# CAN.net
KiCad netlist of a schematic drawn in Altium Designer
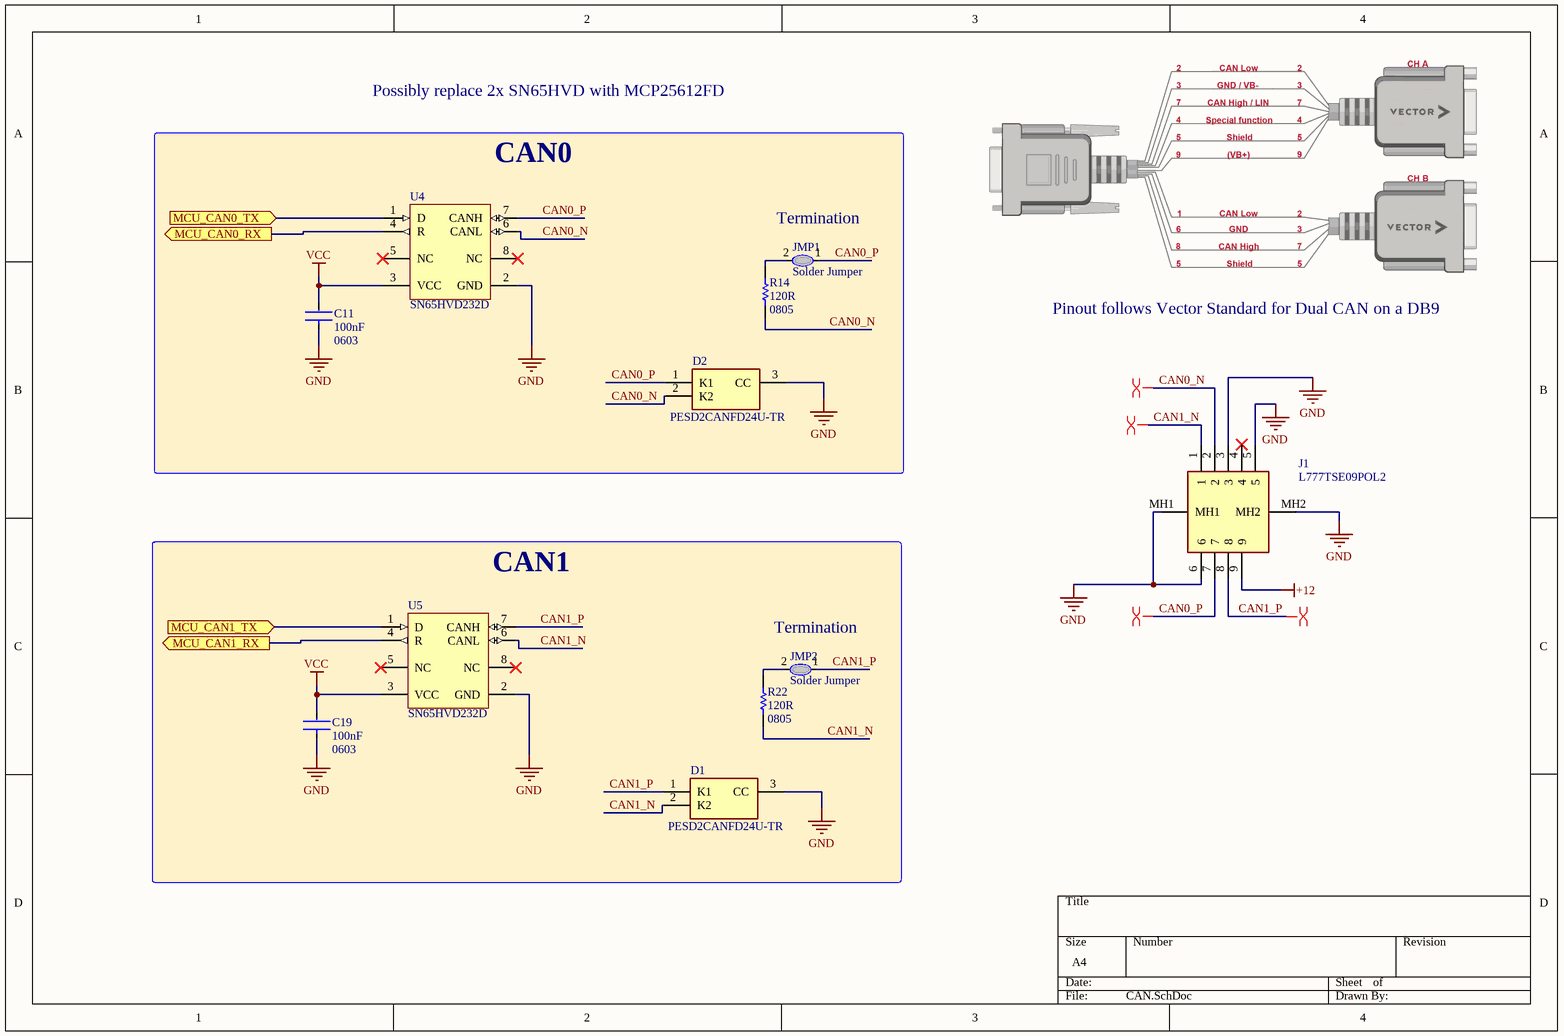
[diagram p0: CAN.SchDoc]

(export (version "E")
  (design (tool "Eeschema 10.0.6"))
  (components
    (comp (ref "C11")
      (value "CL10B104KB8WPNC")
      (footprint "FP-CL10-IPC_A")
      (description "Cap Ceramic 100nF 50V X7R ±10% Pad SMD 0603 +125°C T/R")
      (fields
        (field (name "CAPACITANCE") "100nF")
        (field (name "CASE/PACKAGE") "0603")
        (field (name "TOLERANCE") "10%")
      )
      (libsource (lib "Altium Content Vault") (part "b4654b650e69147ec39a6b967a45e02"))
    )
    (comp (ref "C19")
      (value "CL10B104KB8WPNC")
      (footprint "FP-CL10-IPC_A")
      (description "Cap Ceramic 100nF 50V X7R ±10% Pad SMD 0603 +125°C T/R")
      (fields
        (field (name "CAPACITANCE") "100nF")
        (field (name "CASE/PACKAGE") "0603")
        (field (name "TOLERANCE") "10%")
      )
      (libsource (lib "Altium Content Vault") (part "b4654b650e69147ec39a6b967a45e02"))
    )
    (comp (ref "D1")
      (value "PESD2CANFD24U-TR")
      (footprint "SOT95P230X110-3N")
      (description "Diode")
      (fields (field (name "MOUSER PART NUMBER") "771-PESD2CANFD24U-TR"))
      (libsource (lib "WiCAN_lib") (part "PESD2CANFD24U-TR"))
    )
    (comp (ref "D2")
      (value "PESD2CANFD24U-TR")
      (footprint "SOT95P230X110-3N")
      (description "Diode")
      (fields (field (name "MOUSER PART NUMBER") "771-PESD2CANFD24U-TR"))
      (libsource (lib "WiCAN_lib") (part "PESD2CANFD24U-TR"))
    )
    (comp (ref "J1")
      (value "L777TSE09POL2")
      (footprint "L777TSE09POL2")
      (description "Connector")
      (fields (field (name "MOUSER PART NUMBER") "523-L777TSE09POL2"))
      (libsource (lib "WiCAN_lib") (part "L777TSE09POL2"))
    )
    (comp (ref "JMP1")
      (value "Solder Jumper")
      (footprint "Solder Jumper")
      (libsource (lib "WiCAN_lib") (part "Solder Jumper"))
    )
    (comp (ref "JMP2")
      (value "Solder Jumper")
      (footprint "Solder Jumper")
      (libsource (lib "WiCAN_lib") (part "Solder Jumper"))
    )
    (comp (ref "R14")
      (value "ERJ-P06J121V")
      (footprint "RESC2013X70X40LL20T20")
      (fields
        (field (name "MANUFACTURER") "Panasonic")
        (field (name "RESISTANCE") "120R")
        (field (name "PACKAGE") "0805")
      )
      (libsource (lib "Altium Content Vault") (part "RES"))
    )
    (comp (ref "R22")
      (value "ERJ-P06J121V")
      (footprint "RESC2013X70X40LL20T20")
      (fields
        (field (name "MANUFACTURER") "Panasonic")
        (field (name "RESISTANCE") "120R")
        (field (name "PACKAGE") "0805")
      )
      (libsource (lib "Altium Content Vault") (part "RES"))
    )
    (comp (ref "U4")
      (value "SN65HVD232D")
      (footprint "D0008A_L")
      (description "3.3 V CAN Transceiver, 17 mA, -40 to 85 degC, 8-pin SOIC (D), Green (RoHS & no Sb/Br)")
      (fields (field (name "MANUFACTURER") "Texas Instruments"))
      (libsource (lib "Altium Content Vault") (part "TI-SN65HVD232-SOIC_D-8"))
    )
    (comp (ref "U5")
      (value "SN65HVD232D")
      (footprint "D0008A_L")
      (description "3.3 V CAN Transceiver, 17 mA, -40 to 85 degC, 8-pin SOIC (D), Green (RoHS & no Sb/Br)")
      (fields (field (name "MANUFACTURER") "Texas Instruments"))
      (libsource (lib "Altium Content Vault") (part "TI-SN65HVD232-SOIC_D-8"))
    )
  )
  (nets
    (net (code "1") (name "+12") (class "Default")
      (node (ref "J1") (pin "9") (pinfunction "9_9") (pintype "passive"))
    )
    (net (code "2") (name "/CAN0_N") (class "Default")
      (node (ref "D2") (pin "2") (pinfunction "K2_2") (pintype "passive"))
      (node (ref "J1") (pin "2") (pinfunction "2_2") (pintype "passive"))
      (node (ref "R14") (pin "2") (pinfunction "2_2") (pintype "passive"))
      (node (ref "U4") (pin "6") (pinfunction "CANL_6") (pintype "bidirectional"))
    )
    (net (code "3") (name "/CAN0_P") (class "Default")
      (node (ref "D2") (pin "1") (pinfunction "K1_1") (pintype "passive"))
      (node (ref "J1") (pin "7") (pinfunction "7_7") (pintype "passive"))
      (node (ref "JMP1") (pin "1") (pinfunction "1_1") (pintype "passive"))
      (node (ref "U4") (pin "7") (pinfunction "CANH_7") (pintype "bidirectional"))
    )
    (net (code "4") (name "/CAN1_N") (class "Default")
      (node (ref "D1") (pin "2") (pinfunction "K2_2") (pintype "passive"))
      (node (ref "J1") (pin "1") (pinfunction "1_1") (pintype "passive"))
      (node (ref "R22") (pin "2") (pinfunction "2_2") (pintype "passive"))
      (node (ref "U5") (pin "6") (pinfunction "CANL_6") (pintype "bidirectional"))
    )
    (net (code "5") (name "/CAN1_P") (class "Default")
      (node (ref "D1") (pin "1") (pinfunction "K1_1") (pintype "passive"))
      (node (ref "J1") (pin "8") (pinfunction "8_8") (pintype "passive"))
      (node (ref "JMP2") (pin "1") (pinfunction "1_1") (pintype "passive"))
      (node (ref "U5") (pin "7") (pinfunction "CANH_7") (pintype "bidirectional"))
    )
    (net (code "6") (name "/MCU_CAN0_RX") (class "Default")
      (node (ref "U4") (pin "4") (pinfunction "R_4") (pintype "output"))
    )
    (net (code "7") (name "/MCU_CAN0_TX") (class "Default")
      (node (ref "U4") (pin "1") (pinfunction "D_1") (pintype "input"))
    )
    (net (code "8") (name "/MCU_CAN1_RX") (class "Default")
      (node (ref "U5") (pin "4") (pinfunction "R_4") (pintype "output"))
    )
    (net (code "9") (name "/MCU_CAN1_TX") (class "Default")
      (node (ref "U5") (pin "1") (pinfunction "D_1") (pintype "input"))
    )
    (net (code "10") (name "GND") (class "Default")
      (node (ref "C11") (pin "1") (pinfunction "1_1") (pintype "passive"))
      (node (ref "C19") (pin "1") (pinfunction "1_1") (pintype "passive"))
      (node (ref "D1") (pin "3") (pinfunction "CC_3") (pintype "passive"))
      (node (ref "D2") (pin "3") (pinfunction "CC_3") (pintype "passive"))
      (node (ref "J1") (pin "3") (pinfunction "3_3") (pintype "passive"))
      (node (ref "J1") (pin "5") (pinfunction "5_5") (pintype "passive"))
      (node (ref "J1") (pin "6") (pinfunction "6_6") (pintype "passive"))
      (node (ref "J1") (pin "MH1") (pinfunction "MH1_MH1") (pintype "passive"))
      (node (ref "J1") (pin "MH2") (pinfunction "MH2_MH2") (pintype "passive"))
      (node (ref "U4") (pin "2") (pinfunction "GND_2") (pintype "power_in"))
      (node (ref "U5") (pin "2") (pinfunction "GND_2") (pintype "power_in"))
    )
    (net (code "11") (name "Net-(JMP1-Pad2)") (class "Default")
      (node (ref "JMP1") (pin "2") (pinfunction "2_2") (pintype "passive"))
      (node (ref "R14") (pin "1") (pinfunction "1_1") (pintype "passive"))
    )
    (net (code "12") (name "Net-(JMP2-Pad2)") (class "Default")
      (node (ref "JMP2") (pin "2") (pinfunction "2_2") (pintype "passive"))
      (node (ref "R22") (pin "1") (pinfunction "1_1") (pintype "passive"))
    )
    (net (code "13") (name "VCC") (class "Default")
      (node (ref "C11") (pin "2") (pinfunction "2_2") (pintype "passive"))
      (node (ref "C19") (pin "2") (pinfunction "2_2") (pintype "passive"))
      (node (ref "U4") (pin "3") (pinfunction "VCC_3") (pintype "power_in"))
      (node (ref "U5") (pin "3") (pinfunction "VCC_3") (pintype "power_in"))
    )
    (net (code "14") (name "unconnected-(J1-Pad4)") (class "Default")
      (node (ref "J1") (pin "4") (pinfunction "4_4") (pintype "passive+no_connect"))
    )
    (net (code "15") (name "unconnected-(U4-NC-Pad5)") (class "Default")
      (node (ref "U4") (pin "5") (pinfunction "NC_5") (pintype "passive+no_connect"))
    )
    (net (code "16") (name "unconnected-(U4-NC-Pad8)") (class "Default")
      (node (ref "U4") (pin "8") (pinfunction "NC_8") (pintype "passive+no_connect"))
    )
    (net (code "17") (name "unconnected-(U5-NC-Pad5)") (class "Default")
      (node (ref "U5") (pin "5") (pinfunction "NC_5") (pintype "passive+no_connect"))
    )
    (net (code "18") (name "unconnected-(U5-NC-Pad8)") (class "Default")
      (node (ref "U5") (pin "8") (pinfunction "NC_8") (pintype "passive+no_connect"))
    )
  )
)
